# TPS61020DRCRG4_breakout.net
KiCad netlist of a schematic drawn in EAGLE
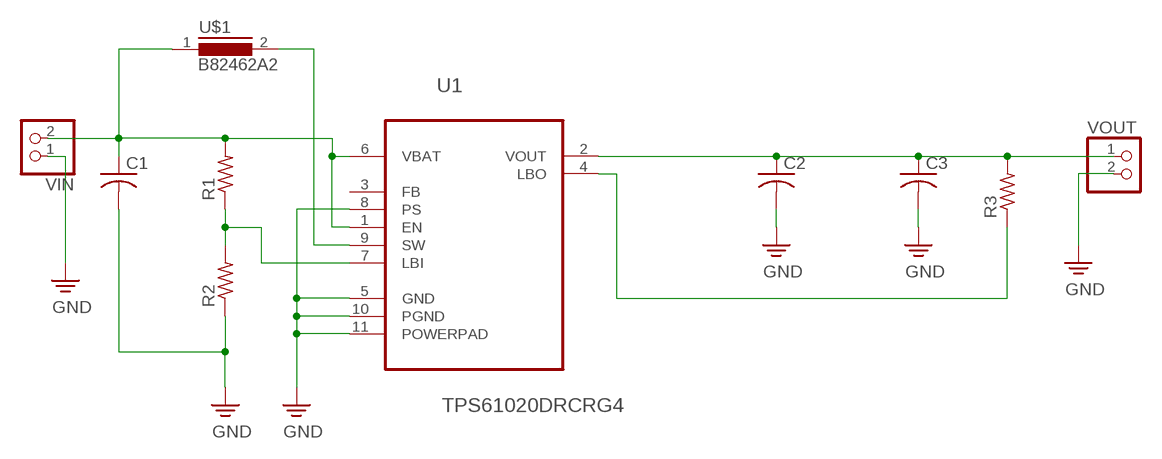
[diagram p0: schematic, sheet 1]

(export (version "E")
  (design (tool "Eeschema 10.0.6"))
  (components
    (comp (ref "C1")
      (value "C-USC0805")
      (footprint "eagle-import:C0805")
      (libsource (lib "eagle-import") (part "C-USC0805"))
    )
    (comp (ref "C2")
      (value "C-USC0805")
      (footprint "eagle-import:C0805")
      (libsource (lib "eagle-import") (part "C-USC0805"))
    )
    (comp (ref "C3")
      (value "C-USC1206")
      (footprint "eagle-import:C1206")
      (libsource (lib "eagle-import") (part "C-USC1206"))
    )
    (comp (ref "R1")
      (value "R-US_R0805")
      (footprint "eagle-import:R0805")
      (libsource (lib "eagle-import") (part "R-US_R0805"))
    )
    (comp (ref "R2")
      (value "R-US_R0805")
      (footprint "eagle-import:R0805")
      (libsource (lib "eagle-import") (part "R-US_R0805"))
    )
    (comp (ref "R3")
      (value "R-US_R0805")
      (footprint "eagle-import:R0805")
      (libsource (lib "eagle-import") (part "R-US_R0805"))
    )
    (comp (ref "U$1")
      (value "B82462A2")
      (footprint "eagle-import:B8246A2682")
      (libsource (lib "eagle-import") (part "B82462A2"))
    )
    (comp (ref "U1")
      (value "TPS61020DRCRG4")
      (footprint "eagle-import:SON50P300X300X100-11N")
      (libsource (lib "eagle-import") (part "TPS61020DRCRG4"))
    )
    (comp (ref "VIN")
      (value "PINHD-1X2")
      (footprint "eagle-import:1X02")
      (libsource (lib "eagle-import") (part "PINHD-1X2"))
    )
    (comp (ref "VOUT")
      (value "PINHD-1X2")
      (footprint "eagle-import:1X02")
      (libsource (lib "eagle-import") (part "PINHD-1X2"))
    )
  )
  (nets
    (net (code "1") (name "GND") (class "Default")
      (node (ref "C1") (pin "2") (pinfunction "2_2") (pintype "passive"))
      (node (ref "C2") (pin "2") (pinfunction "2_2") (pintype "passive"))
      (node (ref "C3") (pin "2") (pinfunction "2_2") (pintype "passive"))
      (node (ref "R2") (pin "1") (pinfunction "1_1") (pintype "passive"))
      (node (ref "U1") (pin "10") (pinfunction "PGND_10") (pintype "passive"))
      (node (ref "U1") (pin "11") (pinfunction "POWERPAD_11") (pintype "passive"))
      (node (ref "U1") (pin "5") (pinfunction "GND_5") (pintype "passive"))
      (node (ref "U1") (pin "8") (pinfunction "PS_8") (pintype "input"))
      (node (ref "VIN") (pin "1") (pinfunction "1_1") (pintype "passive"))
      (node (ref "VOUT") (pin "2") (pinfunction "2_2") (pintype "passive"))
    )
    (net (code "2") (name "Net-(U1-EN)") (class "Default")
      (node (ref "C1") (pin "1") (pinfunction "1_1") (pintype "passive"))
      (node (ref "R1") (pin "2") (pinfunction "2_2") (pintype "passive"))
      (node (ref "U$1") (pin "1") (pinfunction "1_1") (pintype "passive"))
      (node (ref "U1") (pin "1") (pinfunction "EN_1") (pintype "input"))
      (node (ref "U1") (pin "6") (pinfunction "VBAT_6") (pintype "power_in"))
      (node (ref "VIN") (pin "2") (pinfunction "2_2") (pintype "passive"))
    )
    (net (code "3") (name "Net-(U1-LBI)") (class "Default")
      (node (ref "R1") (pin "1") (pinfunction "1_1") (pintype "passive"))
      (node (ref "R2") (pin "2") (pinfunction "2_2") (pintype "passive"))
      (node (ref "U1") (pin "7") (pinfunction "LBI_7") (pintype "input"))
    )
    (net (code "4") (name "Net-(U1-LBO)") (class "Default")
      (node (ref "R3") (pin "1") (pinfunction "1_1") (pintype "passive"))
      (node (ref "U1") (pin "4") (pinfunction "LBO_4") (pintype "output"))
    )
    (net (code "5") (name "Net-(U1-SW)") (class "Default")
      (node (ref "U$1") (pin "2") (pinfunction "2_2") (pintype "passive"))
      (node (ref "U1") (pin "9") (pinfunction "SW_9") (pintype "input"))
    )
    (net (code "6") (name "Net-(U1-VOUT)") (class "Default")
      (node (ref "C2") (pin "1") (pinfunction "1_1") (pintype "passive"))
      (node (ref "C3") (pin "1") (pinfunction "1_1") (pintype "passive"))
      (node (ref "R3") (pin "2") (pinfunction "2_2") (pintype "passive"))
      (node (ref "U1") (pin "2") (pinfunction "VOUT_2") (pintype "output"))
      (node (ref "VOUT") (pin "1") (pinfunction "1_1") (pintype "passive"))
    )
    (net (code "7") (name "unconnected-(U1-FB-Pad3)") (class "Default")
      (node (ref "U1") (pin "3") (pinfunction "FB_3") (pintype "input"))
    )
  )
)
